# SwitchRouter2x3.net
KiCad netlist of a schematic drawn in EAGLE
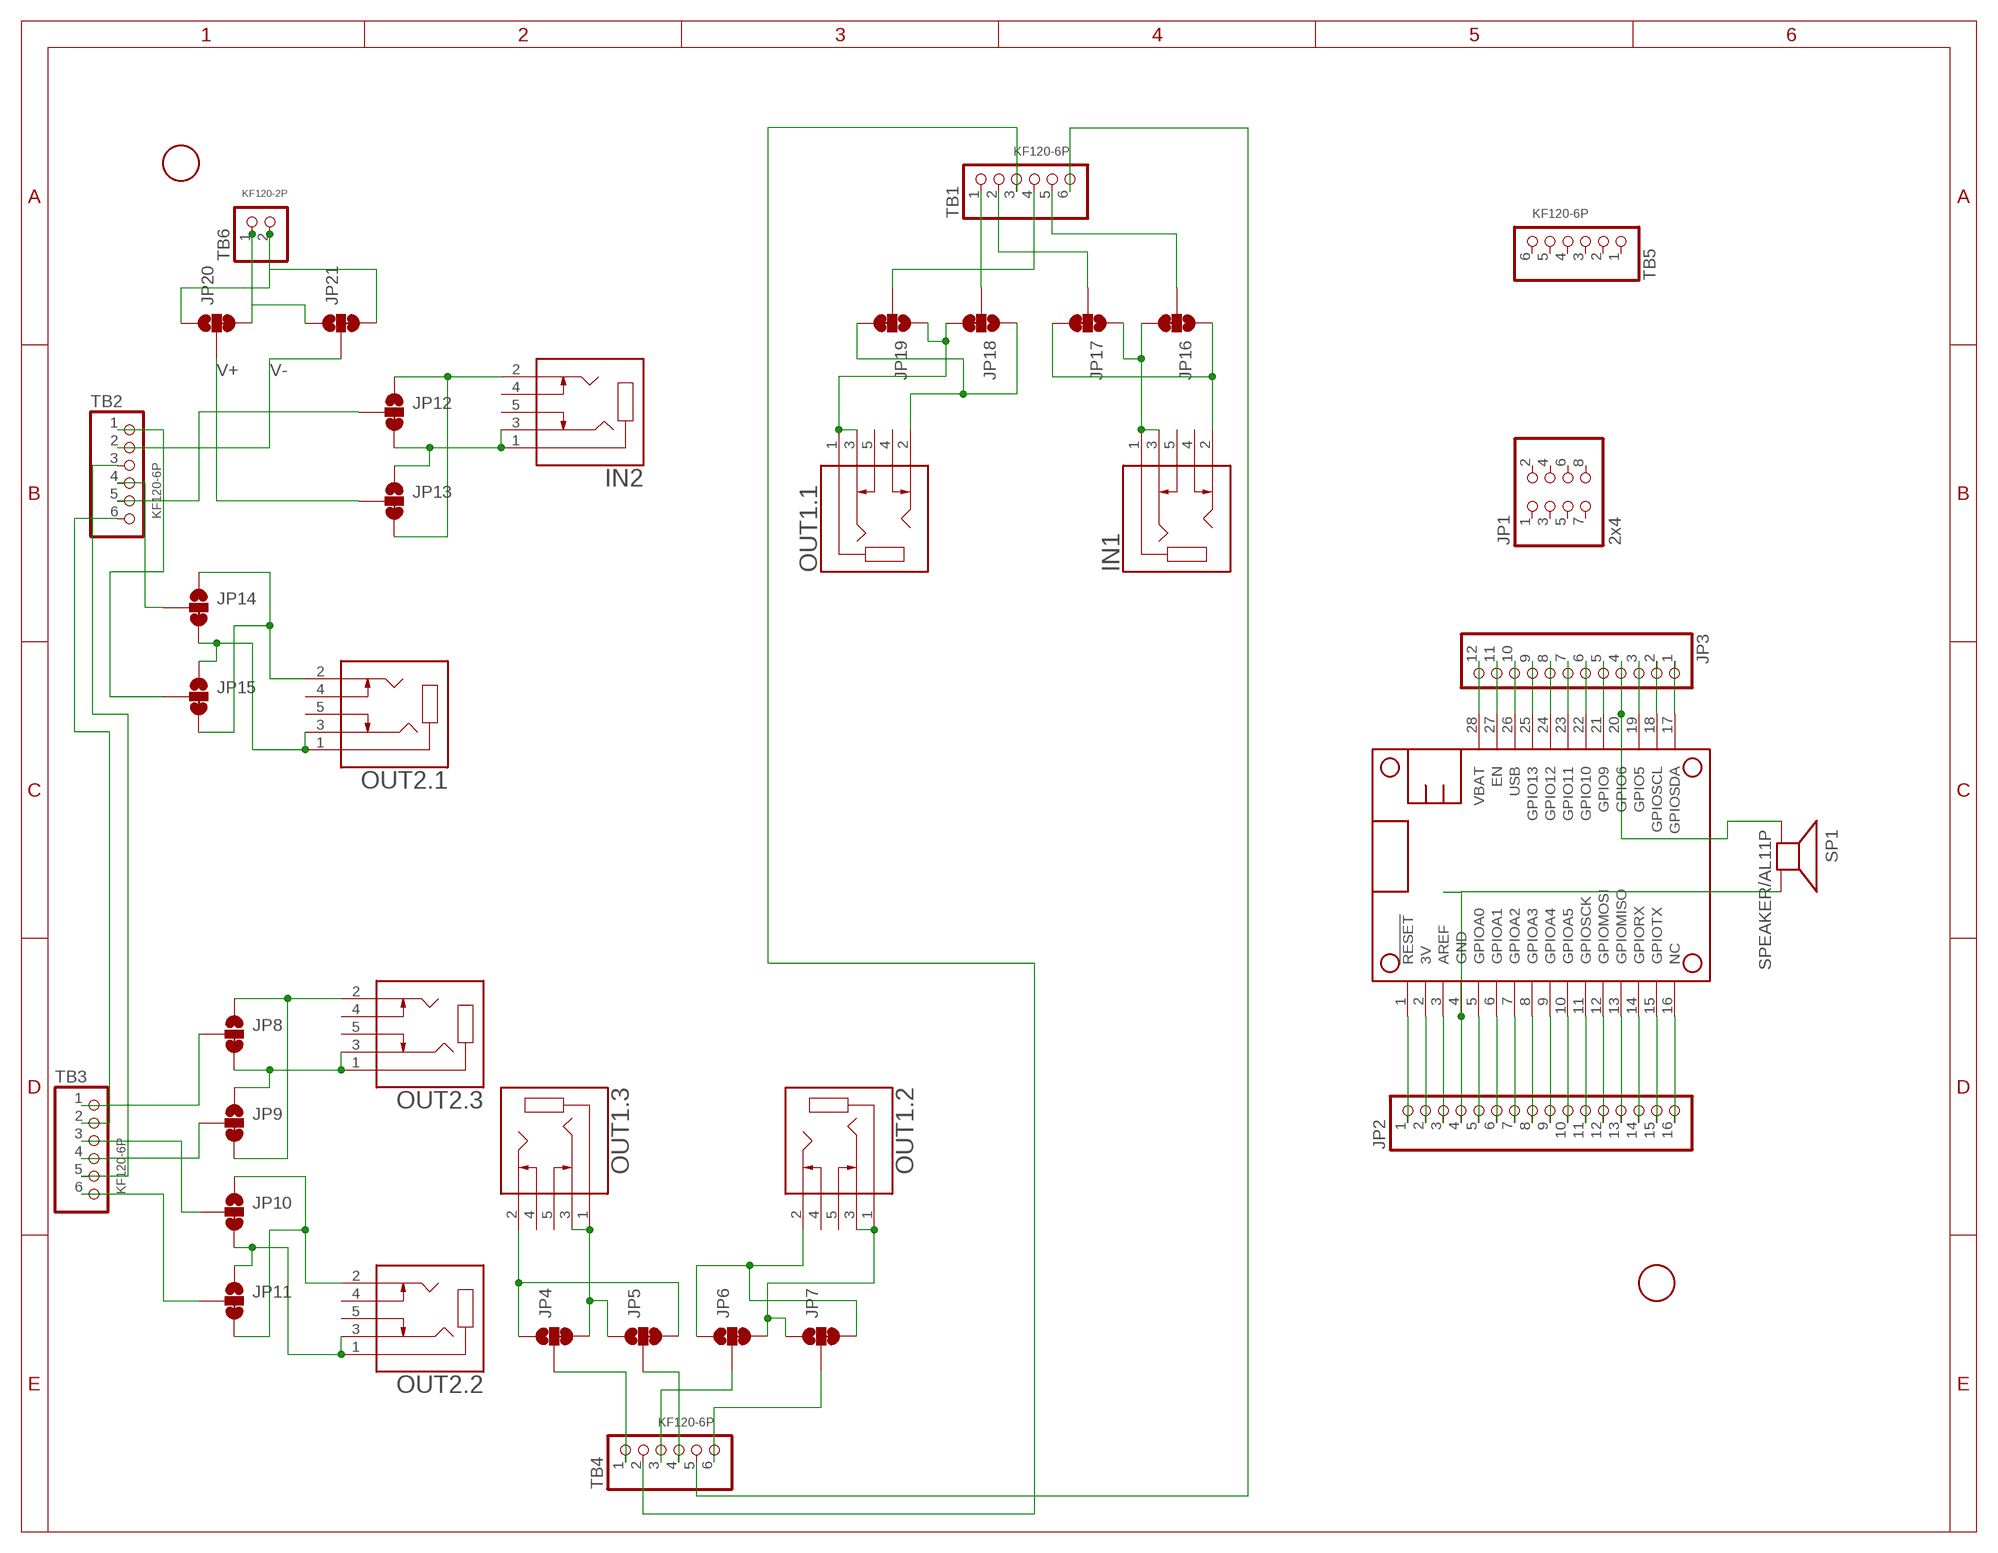
[diagram p0: schematic, sheet 1]

(export (version "E")
  (design (tool "Eeschema 10.0.6"))
  (components
    (comp (ref "IN1")
      (value "SJ1-3535NG-PI")
      (footprint "eagle-import:CUI_SJ1-3535NG-PI")
      (fields (field (name "MANUFACTURER") "CUI"))
      (libsource (lib "eagle-import") (part "SJ1-3535NG-PI"))
    )
    (comp (ref "IN2")
      (value "SJ1-3535NG-PI")
      (footprint "eagle-import:CUI_SJ1-3535NG-PI")
      (fields (field (name "MANUFACTURER") "CUI"))
      (libsource (lib "eagle-import") (part "SJ1-3535NG-PI"))
    )
    (comp (ref "JP1")
      (value "2x4")
      (footprint "eagle-import:2X04")
      (libsource (lib "eagle-import") (part "PINHD-2X4"))
    )
    (comp (ref "JP2")
      (value "PINHD-1X16")
      (footprint "eagle-import:1X16")
      (libsource (lib "eagle-import") (part "PINHD-1X16"))
    )
    (comp (ref "JP3")
      (value "PINHD-1X12")
      (footprint "eagle-import:1X12")
      (libsource (lib "eagle-import") (part "PINHD-1X12"))
    )
    (comp (ref "JP4")
      (value "JUMPER-SMT_3_1-NC_TRACE_SILK")
      (footprint "eagle-import:SMT-JUMPER_3_1-NC_TRACE_SILK")
      (libsource (lib "eagle-import") (part "JUMPER-SMT_3_1-NC_TRACE_SILK"))
    )
    (comp (ref "JP5")
      (value "JUMPER-SMT_3_1-NC_TRACE_SILK")
      (footprint "eagle-import:SMT-JUMPER_3_1-NC_TRACE_SILK")
      (libsource (lib "eagle-import") (part "JUMPER-SMT_3_1-NC_TRACE_SILK"))
    )
    (comp (ref "JP6")
      (value "JUMPER-SMT_3_1-NC_TRACE_SILK")
      (footprint "eagle-import:SMT-JUMPER_3_1-NC_TRACE_SILK")
      (libsource (lib "eagle-import") (part "JUMPER-SMT_3_1-NC_TRACE_SILK"))
    )
    (comp (ref "JP7")
      (value "JUMPER-SMT_3_1-NC_TRACE_SILK")
      (footprint "eagle-import:SMT-JUMPER_3_1-NC_TRACE_SILK")
      (libsource (lib "eagle-import") (part "JUMPER-SMT_3_1-NC_TRACE_SILK"))
    )
    (comp (ref "JP8")
      (value "JUMPER-SMT_3_1-NC_TRACE_SILK")
      (footprint "eagle-import:SMT-JUMPER_3_1-NC_TRACE_SILK")
      (libsource (lib "eagle-import") (part "JUMPER-SMT_3_1-NC_TRACE_SILK"))
    )
    (comp (ref "JP9")
      (value "JUMPER-SMT_3_1-NC_TRACE_SILK")
      (footprint "eagle-import:SMT-JUMPER_3_1-NC_TRACE_SILK")
      (libsource (lib "eagle-import") (part "JUMPER-SMT_3_1-NC_TRACE_SILK"))
    )
    (comp (ref "JP10")
      (value "JUMPER-SMT_3_1-NC_TRACE_SILK")
      (footprint "eagle-import:SMT-JUMPER_3_1-NC_TRACE_SILK")
      (libsource (lib "eagle-import") (part "JUMPER-SMT_3_1-NC_TRACE_SILK"))
    )
    (comp (ref "JP11")
      (value "JUMPER-SMT_3_1-NC_TRACE_SILK")
      (footprint "eagle-import:SMT-JUMPER_3_1-NC_TRACE_SILK")
      (libsource (lib "eagle-import") (part "JUMPER-SMT_3_1-NC_TRACE_SILK"))
    )
    (comp (ref "JP12")
      (value "JUMPER-SMT_3_1-NC_TRACE_SILK")
      (footprint "eagle-import:SMT-JUMPER_3_1-NC_TRACE_SILK")
      (libsource (lib "eagle-import") (part "JUMPER-SMT_3_1-NC_TRACE_SILK"))
    )
    (comp (ref "JP13")
      (value "JUMPER-SMT_3_1-NC_TRACE_SILK")
      (footprint "eagle-import:SMT-JUMPER_3_1-NC_TRACE_SILK")
      (libsource (lib "eagle-import") (part "JUMPER-SMT_3_1-NC_TRACE_SILK"))
    )
    (comp (ref "JP14")
      (value "JUMPER-SMT_3_1-NC_TRACE_SILK")
      (footprint "eagle-import:SMT-JUMPER_3_1-NC_TRACE_SILK")
      (libsource (lib "eagle-import") (part "JUMPER-SMT_3_1-NC_TRACE_SILK"))
    )
    (comp (ref "JP15")
      (value "JUMPER-SMT_3_1-NC_TRACE_SILK")
      (footprint "eagle-import:SMT-JUMPER_3_1-NC_TRACE_SILK")
      (libsource (lib "eagle-import") (part "JUMPER-SMT_3_1-NC_TRACE_SILK"))
    )
    (comp (ref "JP16")
      (value "JUMPER-SMT_3_1-NC_TRACE_SILK")
      (footprint "eagle-import:SMT-JUMPER_3_1-NC_TRACE_SILK")
      (libsource (lib "eagle-import") (part "JUMPER-SMT_3_1-NC_TRACE_SILK"))
    )
    (comp (ref "JP17")
      (value "JUMPER-SMT_3_1-NC_TRACE_SILK")
      (footprint "eagle-import:SMT-JUMPER_3_1-NC_TRACE_SILK")
      (libsource (lib "eagle-import") (part "JUMPER-SMT_3_1-NC_TRACE_SILK"))
    )
    (comp (ref "JP18")
      (value "JUMPER-SMT_3_1-NC_TRACE_SILK")
      (footprint "eagle-import:SMT-JUMPER_3_1-NC_TRACE_SILK")
      (libsource (lib "eagle-import") (part "JUMPER-SMT_3_1-NC_TRACE_SILK"))
    )
    (comp (ref "JP19")
      (value "JUMPER-SMT_3_1-NC_TRACE_SILK")
      (footprint "eagle-import:SMT-JUMPER_3_1-NC_TRACE_SILK")
      (libsource (lib "eagle-import") (part "JUMPER-SMT_3_1-NC_TRACE_SILK"))
    )
    (comp (ref "JP20")
      (value "JUMPER-SMT_3_1-NC_TRACE_SILK")
      (footprint "eagle-import:SMT-JUMPER_3_1-NC_TRACE_SILK")
      (libsource (lib "eagle-import") (part "JUMPER-SMT_3_1-NC_TRACE_SILK"))
    )
    (comp (ref "JP21")
      (value "JUMPER-SMT_3_1-NC_TRACE_SILK")
      (footprint "eagle-import:SMT-JUMPER_3_1-NC_TRACE_SILK")
      (libsource (lib "eagle-import") (part "JUMPER-SMT_3_1-NC_TRACE_SILK"))
    )
    (comp (ref "MS1")
      (value "FEATHERWING_NODIM")
      (footprint "eagle-import:FEATHERWING_DIM")
      (libsource (lib "eagle-import") (part "FEATHERWING_NODIM"))
    )
    (comp (ref "OUT1.1")
      (value "SJ1-3535NG-PI")
      (footprint "eagle-import:CUI_SJ1-3535NG-PI")
      (fields (field (name "MANUFACTURER") "CUI"))
      (libsource (lib "eagle-import") (part "SJ1-3535NG-PI"))
    )
    (comp (ref "OUT1.2")
      (value "SJ1-3535NG-PI")
      (footprint "eagle-import:CUI_SJ1-3535NG-PI")
      (fields (field (name "MANUFACTURER") "CUI"))
      (libsource (lib "eagle-import") (part "SJ1-3535NG-PI"))
    )
    (comp (ref "OUT1.3")
      (value "SJ1-3535NG-PI")
      (footprint "eagle-import:CUI_SJ1-3535NG-PI")
      (fields (field (name "MANUFACTURER") "CUI"))
      (libsource (lib "eagle-import") (part "SJ1-3535NG-PI"))
    )
    (comp (ref "OUT2.1")
      (value "SJ1-3535NG-PI")
      (footprint "eagle-import:CUI_SJ1-3535NG-PI")
      (fields (field (name "MANUFACTURER") "CUI"))
      (libsource (lib "eagle-import") (part "SJ1-3535NG-PI"))
    )
    (comp (ref "OUT2.2")
      (value "SJ1-3535NG-PI")
      (footprint "eagle-import:CUI_SJ1-3535NG-PI")
      (fields (field (name "MANUFACTURER") "CUI"))
      (libsource (lib "eagle-import") (part "SJ1-3535NG-PI"))
    )
    (comp (ref "OUT2.3")
      (value "SJ1-3535NG-PI")
      (footprint "eagle-import:CUI_SJ1-3535NG-PI")
      (fields (field (name "MANUFACTURER") "CUI"))
      (libsource (lib "eagle-import") (part "SJ1-3535NG-PI"))
    )
    (comp (ref "SP1")
      (value "SPEAKER/AL11P")
      (footprint "eagle-import:AL11P")
      (libsource (lib "eagle-import") (part "SPEAKER/AL11P"))
    )
    (comp (ref "TB1")
      (value "KF120-6P")
      (footprint "eagle-import:KF120-6P_ROUND")
      (libsource (lib "eagle-import") (part "KF120-6P"))
    )
    (comp (ref "TB2")
      (value "KF120-6P")
      (footprint "eagle-import:KF120-6P_ROUND")
      (libsource (lib "eagle-import") (part "KF120-6P"))
    )
    (comp (ref "TB3")
      (value "KF120-6P")
      (footprint "eagle-import:KF120-6P_ROUND")
      (libsource (lib "eagle-import") (part "KF120-6P"))
    )
    (comp (ref "TB4")
      (value "KF120-6P")
      (footprint "eagle-import:KF120-6P_ROUND")
      (libsource (lib "eagle-import") (part "KF120-6P"))
    )
    (comp (ref "TB5")
      (value "KF120-6P")
      (footprint "eagle-import:KF120-6P_ROUND")
      (libsource (lib "eagle-import") (part "KF120-6P"))
    )
    (comp (ref "TB6")
      (value "KF120-2P")
      (footprint "eagle-import:KF120-2P_ROUND")
      (libsource (lib "eagle-import") (part "KF120-2P"))
    )
    (comp (ref "U$2")
      (value "FIDUCIAL")
      (footprint "eagle-import:FIDUCIAL_1MM")
      (libsource (lib "eagle-import") (part "FIDUCIAL"))
    )
    (comp (ref "U$3")
      (value "FIDUCIAL")
      (footprint "eagle-import:FIDUCIAL_1MM")
      (libsource (lib "eagle-import") (part "FIDUCIAL"))
    )
  )
  (nets
    (net (code "1") (name "/V+") (class "Default")
      (node (ref "JP13") (pin "2") (pinfunction "2_2") (pintype "passive"))
      (node (ref "JP20") (pin "2") (pinfunction "2_2") (pintype "passive"))
    )
    (net (code "2") (name "/V-") (class "Default")
      (node (ref "JP21") (pin "2") (pinfunction "2_2") (pintype "passive"))
      (node (ref "TB2") (pin "2") (pinfunction "2_2") (pintype "passive"))
    )
    (net (code "3") (name "Net-(IN1-Pad1)") (class "Default")
      (node (ref "IN1") (pin "1") (pinfunction "1_1") (pintype "passive"))
      (node (ref "IN1") (pin "3") (pinfunction "3_3") (pintype "passive"))
      (node (ref "JP16") (pin "3") (pinfunction "3_3") (pintype "passive"))
      (node (ref "JP17") (pin "1") (pinfunction "1_1") (pintype "passive"))
    )
    (net (code "4") (name "Net-(IN1-Pad2)") (class "Default")
      (node (ref "IN1") (pin "2") (pinfunction "2_2") (pintype "passive"))
      (node (ref "JP16") (pin "1") (pinfunction "1_1") (pintype "passive"))
      (node (ref "JP17") (pin "3") (pinfunction "3_3") (pintype "passive"))
    )
    (net (code "5") (name "Net-(IN2-Pad1)") (class "Default")
      (node (ref "IN2") (pin "1") (pinfunction "1_1") (pintype "passive"))
      (node (ref "IN2") (pin "3") (pinfunction "3_3") (pintype "passive"))
      (node (ref "JP12") (pin "3") (pinfunction "3_3") (pintype "passive"))
      (node (ref "JP13") (pin "1") (pinfunction "1_1") (pintype "passive"))
    )
    (net (code "6") (name "Net-(IN2-Pad2)") (class "Default")
      (node (ref "IN2") (pin "2") (pinfunction "2_2") (pintype "passive"))
      (node (ref "JP12") (pin "1") (pinfunction "1_1") (pintype "passive"))
      (node (ref "JP13") (pin "3") (pinfunction "3_3") (pintype "passive"))
    )
    (net (code "7") (name "Net-(JP4-Pad1)") (class "Default")
      (node (ref "JP4") (pin "1") (pinfunction "1_1") (pintype "passive"))
      (node (ref "JP5") (pin "3") (pinfunction "3_3") (pintype "passive"))
      (node (ref "OUT1.3") (pin "2") (pinfunction "2_2") (pintype "passive"))
    )
    (net (code "8") (name "Net-(JP4-Pad2)") (class "Default")
      (node (ref "JP4") (pin "2") (pinfunction "2_2") (pintype "passive"))
      (node (ref "TB4") (pin "1") (pinfunction "1_1") (pintype "passive"))
    )
    (net (code "9") (name "Net-(JP4-Pad3)") (class "Default")
      (node (ref "JP4") (pin "3") (pinfunction "3_3") (pintype "passive"))
      (node (ref "JP5") (pin "1") (pinfunction "1_1") (pintype "passive"))
      (node (ref "OUT1.3") (pin "1") (pinfunction "1_1") (pintype "passive"))
      (node (ref "OUT1.3") (pin "3") (pinfunction "3_3") (pintype "passive"))
    )
    (net (code "10") (name "Net-(JP5-Pad2)") (class "Default")
      (node (ref "JP5") (pin "2") (pinfunction "2_2") (pintype "passive"))
      (node (ref "TB4") (pin "4") (pinfunction "4_4") (pintype "passive"))
    )
    (net (code "11") (name "Net-(JP6-Pad1)") (class "Default")
      (node (ref "JP6") (pin "1") (pinfunction "1_1") (pintype "passive"))
      (node (ref "JP7") (pin "3") (pinfunction "3_3") (pintype "passive"))
      (node (ref "OUT1.2") (pin "2") (pinfunction "2_2") (pintype "passive"))
    )
    (net (code "12") (name "Net-(JP6-Pad2)") (class "Default")
      (node (ref "JP6") (pin "2") (pinfunction "2_2") (pintype "passive"))
      (node (ref "TB4") (pin "3") (pinfunction "3_3") (pintype "passive"))
    )
    (net (code "13") (name "Net-(JP6-Pad3)") (class "Default")
      (node (ref "JP6") (pin "3") (pinfunction "3_3") (pintype "passive"))
      (node (ref "JP7") (pin "1") (pinfunction "1_1") (pintype "passive"))
      (node (ref "OUT1.2") (pin "1") (pinfunction "1_1") (pintype "passive"))
      (node (ref "OUT1.2") (pin "3") (pinfunction "3_3") (pintype "passive"))
    )
    (net (code "14") (name "Net-(JP7-Pad2)") (class "Default")
      (node (ref "JP7") (pin "2") (pinfunction "2_2") (pintype "passive"))
      (node (ref "TB4") (pin "6") (pinfunction "6_6") (pintype "passive"))
    )
    (net (code "15") (name "Net-(JP8-Pad1)") (class "Default")
      (node (ref "JP8") (pin "1") (pinfunction "1_1") (pintype "passive"))
      (node (ref "JP9") (pin "3") (pinfunction "3_3") (pintype "passive"))
      (node (ref "OUT2.3") (pin "2") (pinfunction "2_2") (pintype "passive"))
    )
    (net (code "16") (name "Net-(JP8-Pad2)") (class "Default")
      (node (ref "JP8") (pin "2") (pinfunction "2_2") (pintype "passive"))
      (node (ref "TB3") (pin "1") (pinfunction "1_1") (pintype "passive"))
    )
    (net (code "17") (name "Net-(JP8-Pad3)") (class "Default")
      (node (ref "JP8") (pin "3") (pinfunction "3_3") (pintype "passive"))
      (node (ref "JP9") (pin "1") (pinfunction "1_1") (pintype "passive"))
      (node (ref "OUT2.3") (pin "1") (pinfunction "1_1") (pintype "passive"))
      (node (ref "OUT2.3") (pin "3") (pinfunction "3_3") (pintype "passive"))
    )
    (net (code "18") (name "Net-(JP9-Pad2)") (class "Default")
      (node (ref "JP9") (pin "2") (pinfunction "2_2") (pintype "passive"))
      (node (ref "TB3") (pin "4") (pinfunction "4_4") (pintype "passive"))
    )
    (net (code "19") (name "Net-(JP10-Pad1)") (class "Default")
      (node (ref "JP10") (pin "1") (pinfunction "1_1") (pintype "passive"))
      (node (ref "JP11") (pin "3") (pinfunction "3_3") (pintype "passive"))
      (node (ref "OUT2.2") (pin "2") (pinfunction "2_2") (pintype "passive"))
    )
    (net (code "20") (name "Net-(JP10-Pad2)") (class "Default")
      (node (ref "JP10") (pin "2") (pinfunction "2_2") (pintype "passive"))
      (node (ref "TB3") (pin "3") (pinfunction "3_3") (pintype "passive"))
    )
    (net (code "21") (name "Net-(JP10-Pad3)") (class "Default")
      (node (ref "JP10") (pin "3") (pinfunction "3_3") (pintype "passive"))
      (node (ref "JP11") (pin "1") (pinfunction "1_1") (pintype "passive"))
      (node (ref "OUT2.2") (pin "1") (pinfunction "1_1") (pintype "passive"))
      (node (ref "OUT2.2") (pin "3") (pinfunction "3_3") (pintype "passive"))
    )
    (net (code "22") (name "Net-(JP11-Pad2)") (class "Default")
      (node (ref "JP11") (pin "2") (pinfunction "2_2") (pintype "passive"))
      (node (ref "TB3") (pin "6") (pinfunction "6_6") (pintype "passive"))
    )
    (net (code "23") (name "Net-(JP12-Pad2)") (class "Default")
      (node (ref "JP12") (pin "2") (pinfunction "2_2") (pintype "passive"))
      (node (ref "TB2") (pin "5") (pinfunction "5_5") (pintype "passive"))
    )
    (net (code "24") (name "Net-(JP14-Pad1)") (class "Default")
      (node (ref "JP14") (pin "1") (pinfunction "1_1") (pintype "passive"))
      (node (ref "JP15") (pin "3") (pinfunction "3_3") (pintype "passive"))
      (node (ref "OUT2.1") (pin "2") (pinfunction "2_2") (pintype "passive"))
    )
    (net (code "25") (name "Net-(JP14-Pad2)") (class "Default")
      (node (ref "JP14") (pin "2") (pinfunction "2_2") (pintype "passive"))
      (node (ref "TB2") (pin "4") (pinfunction "4_4") (pintype "passive"))
    )
    (net (code "26") (name "Net-(JP14-Pad3)") (class "Default")
      (node (ref "JP14") (pin "3") (pinfunction "3_3") (pintype "passive"))
      (node (ref "JP15") (pin "1") (pinfunction "1_1") (pintype "passive"))
      (node (ref "OUT2.1") (pin "1") (pinfunction "1_1") (pintype "passive"))
      (node (ref "OUT2.1") (pin "3") (pinfunction "3_3") (pintype "passive"))
    )
    (net (code "27") (name "Net-(JP15-Pad2)") (class "Default")
      (node (ref "JP15") (pin "2") (pinfunction "2_2") (pintype "passive"))
      (node (ref "TB2") (pin "1") (pinfunction "1_1") (pintype "passive"))
    )
    (net (code "28") (name "Net-(JP16-Pad2)") (class "Default")
      (node (ref "JP16") (pin "2") (pinfunction "2_2") (pintype "passive"))
      (node (ref "TB1") (pin "5") (pinfunction "5_5") (pintype "passive"))
    )
    (net (code "29") (name "Net-(JP17-Pad2)") (class "Default")
      (node (ref "JP17") (pin "2") (pinfunction "2_2") (pintype "passive"))
      (node (ref "TB1") (pin "2") (pinfunction "2_2") (pintype "passive"))
    )
    (net (code "30") (name "Net-(JP18-Pad1)") (class "Default")
      (node (ref "JP18") (pin "1") (pinfunction "1_1") (pintype "passive"))
      (node (ref "JP19") (pin "3") (pinfunction "3_3") (pintype "passive"))
      (node (ref "OUT1.1") (pin "2") (pinfunction "2_2") (pintype "passive"))
    )
    (net (code "31") (name "Net-(JP18-Pad2)") (class "Default")
      (node (ref "JP18") (pin "2") (pinfunction "2_2") (pintype "passive"))
      (node (ref "TB1") (pin "1") (pinfunction "1_1") (pintype "passive"))
    )
    (net (code "32") (name "Net-(JP18-Pad3)") (class "Default")
      (node (ref "JP18") (pin "3") (pinfunction "3_3") (pintype "passive"))
      (node (ref "JP19") (pin "1") (pinfunction "1_1") (pintype "passive"))
      (node (ref "OUT1.1") (pin "1") (pinfunction "1_1") (pintype "passive"))
      (node (ref "OUT1.1") (pin "3") (pinfunction "3_3") (pintype "passive"))
    )
    (net (code "33") (name "Net-(JP19-Pad2)") (class "Default")
      (node (ref "JP19") (pin "2") (pinfunction "2_2") (pintype "passive"))
      (node (ref "TB1") (pin "4") (pinfunction "4_4") (pintype "passive"))
    )
    (net (code "34") (name "Net-(JP20-Pad1)") (class "Default")
      (node (ref "JP20") (pin "1") (pinfunction "1_1") (pintype "passive"))
      (node (ref "JP21") (pin "3") (pinfunction "3_3") (pintype "passive"))
      (node (ref "TB6") (pin "2") (pinfunction "2_2") (pintype "passive"))
    )
    (net (code "35") (name "Net-(JP20-Pad3)") (class "Default")
      (node (ref "JP20") (pin "3") (pinfunction "3_3") (pintype "passive"))
      (node (ref "JP21") (pin "1") (pinfunction "1_1") (pintype "passive"))
      (node (ref "TB6") (pin "1") (pinfunction "1_1") (pintype "passive"))
    )
    (net (code "36") (name "Net-(MS1-3V)") (class "Default")
      (node (ref "JP2") (pin "2") (pinfunction "2_2") (pintype "passive"))
      (node (ref "MS1") (pin "2") (pinfunction "3V_2") (pintype "power_in"))
    )
    (net (code "37") (name "Net-(MS1-AREF)") (class "Default")
      (node (ref "JP2") (pin "3") (pinfunction "3_3") (pintype "passive"))
      (node (ref "MS1") (pin "3") (pinfunction "AREF_3") (pintype "passive"))
    )
    (net (code "38") (name "Net-(MS1-EN)") (class "Default")
      (node (ref "JP3") (pin "11") (pinfunction "11_11") (pintype "passive"))
      (node (ref "MS1") (pin "27") (pinfunction "EN_27") (pintype "passive"))
    )
    (net (code "39") (name "Net-(MS1-GND)") (class "Default")
      (node (ref "JP2") (pin "4") (pinfunction "4_4") (pintype "passive"))
      (node (ref "MS1") (pin "4") (pinfunction "GND_4") (pintype "power_in"))
      (node (ref "SP1") (pin "-") (pinfunction "-_-") (pintype "passive"))
    )
    (net (code "40") (name "Net-(MS1-GPIO5)") (class "Default")
      (node (ref "JP3") (pin "3") (pinfunction "3_3") (pintype "passive"))
      (node (ref "MS1") (pin "19") (pinfunction "GPIO5_19") (pintype "bidirectional"))
    )
    (net (code "41") (name "Net-(MS1-GPIO6)") (class "Default")
      (node (ref "JP3") (pin "4") (pinfunction "4_4") (pintype "passive"))
      (node (ref "MS1") (pin "20") (pinfunction "GPIO6_20") (pintype "bidirectional"))
      (node (ref "SP1") (pin "+") (pinfunction "+_+") (pintype "passive"))
    )
    (net (code "42") (name "Net-(MS1-GPIO9)") (class "Default")
      (node (ref "JP3") (pin "5") (pinfunction "5_5") (pintype "passive"))
      (node (ref "MS1") (pin "21") (pinfunction "GPIO9_21") (pintype "bidirectional"))
    )
    (net (code "43") (name "Net-(MS1-GPIO10)") (class "Default")
      (node (ref "JP3") (pin "6") (pinfunction "6_6") (pintype "passive"))
      (node (ref "MS1") (pin "22") (pinfunction "GPIO10_22") (pintype "bidirectional"))
    )
    (net (code "44") (name "Net-(MS1-GPIO11)") (class "Default")
      (node (ref "JP3") (pin "7") (pinfunction "7_7") (pintype "passive"))
      (node (ref "MS1") (pin "23") (pinfunction "GPIO11_23") (pintype "bidirectional"))
    )
    (net (code "45") (name "Net-(MS1-GPIO12)") (class "Default")
      (node (ref "JP3") (pin "8") (pinfunction "8_8") (pintype "passive"))
      (node (ref "MS1") (pin "24") (pinfunction "GPIO12_24") (pintype "bidirectional"))
    )
    (net (code "46") (name "Net-(MS1-GPIO13)") (class "Default")
      (node (ref "JP3") (pin "9") (pinfunction "9_9") (pintype "passive"))
      (node (ref "MS1") (pin "25") (pinfunction "GPIO13_25") (pintype "bidirectional"))
    )
    (net (code "47") (name "Net-(MS1-GPIOA0)") (class "Default")
      (node (ref "JP2") (pin "5") (pinfunction "5_5") (pintype "passive"))
      (node (ref "MS1") (pin "5") (pinfunction "GPIOA0_5") (pintype "bidirectional"))
    )
    (net (code "48") (name "Net-(MS1-GPIOA1)") (class "Default")
      (node (ref "JP2") (pin "6") (pinfunction "6_6") (pintype "passive"))
      (node (ref "MS1") (pin "6") (pinfunction "GPIOA1_6") (pintype "bidirectional"))
    )
    (net (code "49") (name "Net-(MS1-GPIOA2)") (class "Default")
      (node (ref "JP2") (pin "7") (pinfunction "7_7") (pintype "passive"))
      (node (ref "MS1") (pin "7") (pinfunction "GPIOA2_7") (pintype "bidirectional"))
    )
    (net (code "50") (name "Net-(MS1-GPIOA3)") (class "Default")
      (node (ref "JP2") (pin "8") (pinfunction "8_8") (pintype "passive"))
      (node (ref "MS1") (pin "8") (pinfunction "GPIOA3_8") (pintype "bidirectional"))
    )
    (net (code "51") (name "Net-(MS1-GPIOA4)") (class "Default")
      (node (ref "JP2") (pin "9") (pinfunction "9_9") (pintype "passive"))
      (node (ref "MS1") (pin "9") (pinfunction "GPIOA4_9") (pintype "bidirectional"))
    )
    (net (code "52") (name "Net-(MS1-GPIOA5)") (class "Default")
      (node (ref "JP2") (pin "10") (pinfunction "10_10") (pintype "passive"))
      (node (ref "MS1") (pin "10") (pinfunction "GPIOA5_10") (pintype "bidirectional"))
    )
    (net (code "53") (name "Net-(MS1-GPIOMISO)") (class "Default")
      (node (ref "JP2") (pin "13") (pinfunction "13_13") (pintype "passive"))
      (node (ref "MS1") (pin "13") (pinfunction "GPIOMISO_13") (pintype "bidirectional"))
    )
    (net (code "54") (name "Net-(MS1-GPIOMOSI)") (class "Default")
      (node (ref "JP2") (pin "12") (pinfunction "12_12") (pintype "passive"))
      (node (ref "MS1") (pin "12") (pinfunction "GPIOMOSI_12") (pintype "bidirectional"))
    )
    (net (code "55") (name "Net-(MS1-GPIORX)") (class "Default")
      (node (ref "JP2") (pin "14") (pinfunction "14_14") (pintype "passive"))
      (node (ref "MS1") (pin "14") (pinfunction "GPIORX_14") (pintype "bidirectional"))
    )
    (net (code "56") (name "Net-(MS1-GPIOSCK)") (class "Default")
      (node (ref "JP2") (pin "11") (pinfunction "11_11") (pintype "passive"))
      (node (ref "MS1") (pin "11") (pinfunction "GPIOSCK_11") (pintype "bidirectional"))
    )
    (net (code "57") (name "Net-(MS1-GPIOSCL)") (class "Default")
      (node (ref "JP3") (pin "2") (pinfunction "2_2") (pintype "passive"))
      (node (ref "MS1") (pin "18") (pinfunction "GPIOSCL_18") (pintype "bidirectional"))
    )
    (net (code "58") (name "Net-(MS1-GPIOSDA)") (class "Default")
      (node (ref "JP3") (pin "1") (pinfunction "1_1") (pintype "passive"))
      (node (ref "MS1") (pin "17") (pinfunction "GPIOSDA_17") (pintype "bidirectional"))
    )
    (net (code "59") (name "Net-(MS1-GPIOTX)") (class "Default")
      (node (ref "JP2") (pin "15") (pinfunction "15_15") (pintype "passive"))
      (node (ref "MS1") (pin "15") (pinfunction "GPIOTX_15") (pintype "bidirectional"))
    )
    (net (code "60") (name "Net-(MS1-NC)") (class "Default")
      (node (ref "JP2") (pin "16") (pinfunction "16_16") (pintype "passive"))
      (node (ref "MS1") (pin "16") (pinfunction "NC_16") (pintype "passive"))
    )
    (net (code "61") (name "Net-(MS1-USB)") (class "Default")
      (node (ref "JP3") (pin "10") (pinfunction "10_10") (pintype "passive"))
      (node (ref "MS1") (pin "26") (pinfunction "USB_26") (pintype "power_in"))
    )
    (net (code "62") (name "Net-(MS1-VBAT)") (class "Default")
      (node (ref "JP3") (pin "12") (pinfunction "12_12") (pintype "passive"))
      (node (ref "MS1") (pin "28") (pinfunction "VBAT_28") (pintype "power_in"))
    )
    (net (code "63") (name "Net-(MS1-~{RESET})") (class "Default")
      (node (ref "JP2") (pin "1") (pinfunction "1_1") (pintype "passive"))
      (node (ref "MS1") (pin "1") (pinfunction "~{RESET}_1") (pintype "input"))
    )
    (net (code "64") (name "Net-(TB1-Pad3)") (class "Default")
      (node (ref "TB1") (pin "3") (pinfunction "3_3") (pintype "passive"))
      (node (ref "TB4") (pin "2") (pinfunction "2_2") (pintype "passive"))
    )
    (net (code "65") (name "Net-(TB1-Pad6)") (class "Default")
      (node (ref "TB1") (pin "6") (pinfunction "6_6") (pintype "passive"))
      (node (ref "TB4") (pin "5") (pinfunction "5_5") (pintype "passive"))
    )
    (net (code "66") (name "Net-(TB2-Pad3)") (class "Default")
      (node (ref "TB2") (pin "3") (pinfunction "3_3") (pintype "passive"))
      (node (ref "TB3") (pin "5") (pinfunction "5_5") (pintype "passive"))
    )
    (net (code "67") (name "Net-(TB2-Pad6)") (class "Default")
      (node (ref "TB2") (pin "6") (pinfunction "6_6") (pintype "passive"))
      (node (ref "TB3") (pin "2") (pinfunction "2_2") (pintype "passive"))
    )
    (net (code "68") (name "unconnected-(IN1-Pad4)") (class "Default")
      (node (ref "IN1") (pin "4") (pinfunction "4_4") (pintype "passive"))
    )
    (net (code "69") (name "unconnected-(IN1-Pad5)") (class "Default")
      (node (ref "IN1") (pin "5") (pinfunction "5_5") (pintype "passive"))
    )
    (net (code "70") (name "unconnected-(IN2-Pad4)") (class "Default")
      (node (ref "IN2") (pin "4") (pinfunction "4_4") (pintype "passive"))
    )
    (net (code "71") (name "unconnected-(IN2-Pad5)") (class "Default")
      (node (ref "IN2") (pin "5") (pinfunction "5_5") (pintype "passive"))
    )
    (net (code "72") (name "unconnected-(JP1-Pad1)") (class "Default")
      (node (ref "JP1") (pin "1") (pinfunction "1_1") (pintype "passive"))
    )
    (net (code "73") (name "unconnected-(JP1-Pad2)") (class "Default")
      (node (ref "JP1") (pin "2") (pinfunction "2_2") (pintype "passive"))
    )
    (net (code "74") (name "unconnected-(JP1-Pad3)") (class "Default")
      (node (ref "JP1") (pin "3") (pinfunction "3_3") (pintype "passive"))
    )
    (net (code "75") (name "unconnected-(JP1-Pad4)") (class "Default")
      (node (ref "JP1") (pin "4") (pinfunction "4_4") (pintype "passive"))
    )
    (net (code "76") (name "unconnected-(JP1-Pad5)") (class "Default")
      (node (ref "JP1") (pin "5") (pinfunction "5_5") (pintype "passive"))
    )
    (net (code "77") (name "unconnected-(JP1-Pad6)") (class "Default")
      (node (ref "JP1") (pin "6") (pinfunction "6_6") (pintype "passive"))
    )
    (net (code "78") (name "unconnected-(JP1-Pad7)") (class "Default")
      (node (ref "JP1") (pin "7") (pinfunction "7_7") (pintype "passive"))
    )
    (net (code "79") (name "unconnected-(JP1-Pad8)") (class "Default")
      (node (ref "JP1") (pin "8") (pinfunction "8_8") (pintype "passive"))
    )
    (net (code "80") (name "unconnected-(OUT1.1-Pad4)") (class "Default")
      (node (ref "OUT1.1") (pin "4") (pinfunction "4_4") (pintype "passive"))
    )
    (net (code "81") (name "unconnected-(OUT1.1-Pad5)") (class "Default")
      (node (ref "OUT1.1") (pin "5") (pinfunction "5_5") (pintype "passive"))
    )
    (net (code "82") (name "unconnected-(OUT1.2-Pad4)") (class "Default")
      (node (ref "OUT1.2") (pin "4") (pinfunction "4_4") (pintype "passive"))
    )
    (net (code "83") (name "unconnected-(OUT1.2-Pad5)") (class "Default")
      (node (ref "OUT1.2") (pin "5") (pinfunction "5_5") (pintype "passive"))
    )
    (net (code "84") (name "unconnected-(OUT1.3-Pad4)") (class "Default")
      (node (ref "OUT1.3") (pin "4") (pinfunction "4_4") (pintype "passive"))
    )
    (net (code "85") (name "unconnected-(OUT1.3-Pad5)") (class "Default")
      (node (ref "OUT1.3") (pin "5") (pinfunction "5_5") (pintype "passive"))
    )
    (net (code "86") (name "unconnected-(OUT2.1-Pad4)") (class "Default")
      (node (ref "OUT2.1") (pin "4") (pinfunction "4_4") (pintype "passive"))
    )
    (net (code "87") (name "unconnected-(OUT2.1-Pad5)") (class "Default")
      (node (ref "OUT2.1") (pin "5") (pinfunction "5_5") (pintype "passive"))
    )
    (net (code "88") (name "unconnected-(OUT2.2-Pad4)") (class "Default")
      (node (ref "OUT2.2") (pin "4") (pinfunction "4_4") (pintype "passive"))
    )
    (net (code "89") (name "unconnected-(OUT2.2-Pad5)") (class "Default")
      (node (ref "OUT2.2") (pin "5") (pinfunction "5_5") (pintype "passive"))
    )
    (net (code "90") (name "unconnected-(OUT2.3-Pad4)") (class "Default")
      (node (ref "OUT2.3") (pin "4") (pinfunction "4_4") (pintype "passive"))
    )
    (net (code "91") (name "unconnected-(OUT2.3-Pad5)") (class "Default")
      (node (ref "OUT2.3") (pin "5") (pinfunction "5_5") (pintype "passive"))
    )
    (net (code "92") (name "unconnected-(TB5-Pad1)") (class "Default")
      (node (ref "TB5") (pin "1") (pinfunction "1_1") (pintype "passive"))
    )
    (net (code "93") (name "unconnected-(TB5-Pad2)") (class "Default")
      (node (ref "TB5") (pin "2") (pinfunction "2_2") (pintype "passive"))
    )
    (net (code "94") (name "unconnected-(TB5-Pad3)") (class "Default")
      (node (ref "TB5") (pin "3") (pinfunction "3_3") (pintype "passive"))
    )
    (net (code "95") (name "unconnected-(TB5-Pad4)") (class "Default")
      (node (ref "TB5") (pin "4") (pinfunction "4_4") (pintype "passive"))
    )
    (net (code "96") (name "unconnected-(TB5-Pad5)") (class "Default")
      (node (ref "TB5") (pin "5") (pinfunction "5_5") (pintype "passive"))
    )
    (net (code "97") (name "unconnected-(TB5-Pad6)") (class "Default")
      (node (ref "TB5") (pin "6") (pinfunction "6_6") (pintype "passive"))
    )
  )
)
